# usb_board.net
KiCad netlist of a schematic drawn in Altium Designer
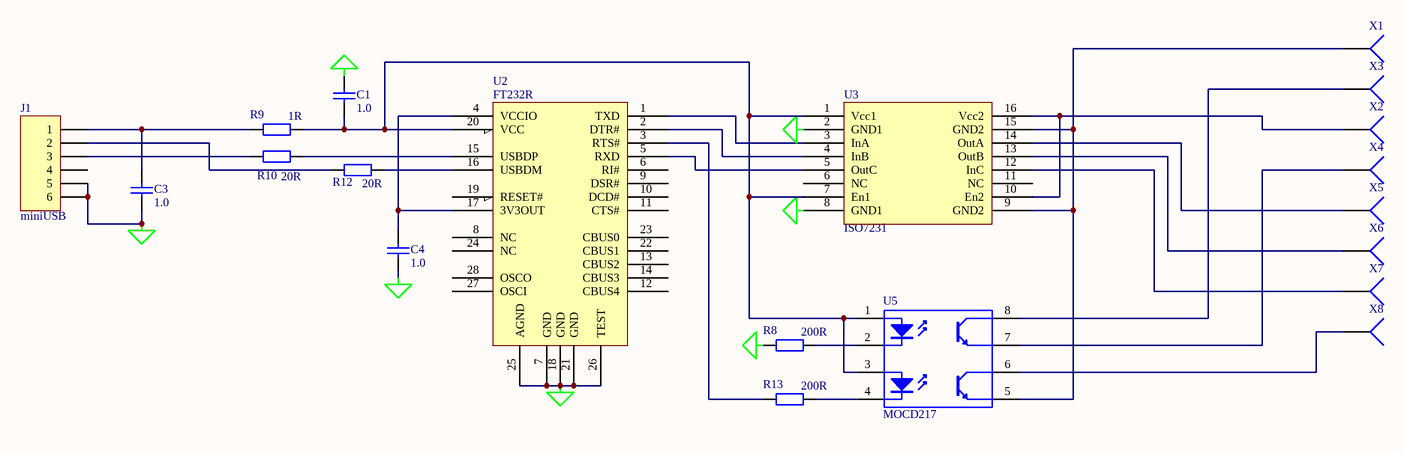
[diagram p0: usb_board.SchDoc]

(export (version "E")
  (design (tool "Eeschema 10.0.6"))
  (components
    (comp (ref "C1")
      (value "1.0")
      (footprint "_0603")
      (description "Capacitor (Semiconductor SIM Model)")
      (fields (field (name "MANUFACTURER") "Generic Components") (field (name "PUBLISHER") "Altium Limited"))
      (libsource (lib "Miscellaneous Devices") (part "Cap Semi"))
    )
    (comp (ref "C3")
      (value "1.0")
      (footprint "_0603")
      (description "Capacitor (Semiconductor SIM Model)")
      (fields (field (name "MANUFACTURER") "Generic Components") (field (name "PUBLISHER") "Altium Limited"))
      (libsource (lib "Miscellaneous Devices") (part "Cap Semi"))
    )
    (comp (ref "C4")
      (value "1.0")
      (footprint "_0603")
      (description "Capacitor (Semiconductor SIM Model)")
      (fields (field (name "MANUFACTURER") "Generic Components") (field (name "PUBLISHER") "Altium Limited"))
      (libsource (lib "Miscellaneous Devices") (part "Cap Semi"))
    )
    (comp (ref "J1")
      (value "miniUSB")
      (footprint "USBmini")
      (description "Header, 6-Pin")
      (fields (field (name "PUBLISHER") "Altium Limited"))
      (libsource (lib "Miscellaneous Connectors") (part "Header 6"))
    )
    (comp (ref "R8") (value "200R") (footprint "_0603") (libsource (lib "igorenja") (part "RES")))
    (comp (ref "R9") (value "1R") (footprint "_0603") (libsource (lib "igorenja") (part "RES")))
    (comp (ref "R10") (value "20R") (footprint "_0603") (libsource (lib "igorenja") (part "RES")))
    (comp (ref "R12") (value "20R") (footprint "_0603") (libsource (lib "igorenja") (part "RES")))
    (comp (ref "R13") (value "200R") (footprint "_0603") (libsource (lib "igorenja") (part "RES")))
    (comp (ref "U2")
      (value "FT232R")
      (footprint "SOP65P780-28L")
      (libsource (lib "igorenja") (part "FT232R"))
    )
    (comp (ref "U3") (value "ISO7231") (libsource (lib "PAL") (part "ISO7231")))
    (comp (ref "U5")
      (value "MOCD217")
      (footprint "SO-G8")
      (description "Optic")
      (libsource (lib "PAL") (part "MOCD217"))
    )
    (comp (ref "X1")
      (value "~")
      (footprint "PIN1")
      (description "Socket")
      (fields (field (name "MANUFACTURER") "Generic Components") (field (name "PUBLISHER") "Altium Limited"))
      (libsource (lib "Miscellaneous Connectors") (part "Socket"))
    )
    (comp (ref "X2")
      (value "~")
      (footprint "PIN1")
      (description "Socket")
      (fields (field (name "MANUFACTURER") "Generic Components") (field (name "PUBLISHER") "Altium Limited"))
      (libsource (lib "Miscellaneous Connectors") (part "Socket"))
    )
    (comp (ref "X3")
      (value "~")
      (footprint "PIN1")
      (description "Socket")
      (fields (field (name "MANUFACTURER") "Generic Components") (field (name "PUBLISHER") "Altium Limited"))
      (libsource (lib "Miscellaneous Connectors") (part "Socket"))
    )
    (comp (ref "X4")
      (value "~")
      (footprint "PIN1")
      (description "Socket")
      (fields (field (name "MANUFACTURER") "Generic Components") (field (name "PUBLISHER") "Altium Limited"))
      (libsource (lib "Miscellaneous Connectors") (part "Socket"))
    )
    (comp (ref "X5")
      (value "~")
      (footprint "PIN1")
      (description "Socket")
      (fields (field (name "MANUFACTURER") "Generic Components") (field (name "PUBLISHER") "Altium Limited"))
      (libsource (lib "Miscellaneous Connectors") (part "Socket"))
    )
    (comp (ref "X6")
      (value "~")
      (footprint "PIN1")
      (description "Socket")
      (fields (field (name "MANUFACTURER") "Generic Components") (field (name "PUBLISHER") "Altium Limited"))
      (libsource (lib "Miscellaneous Connectors") (part "Socket"))
    )
    (comp (ref "X7")
      (value "~")
      (footprint "PIN1")
      (description "Socket")
      (fields (field (name "MANUFACTURER") "Generic Components") (field (name "PUBLISHER") "Altium Limited"))
      (libsource (lib "Miscellaneous Connectors") (part "Socket"))
    )
    (comp (ref "X8")
      (value "~")
      (footprint "PIN1")
      (description "Socket")
      (fields (field (name "MANUFACTURER") "Generic Components") (field (name "PUBLISHER") "Altium Limited"))
      (libsource (lib "Miscellaneous Connectors") (part "Socket"))
    )
  )
  (nets
    (net (code "1") (name "GND_USB") (class "Default")
      (node (ref "C1") (pin "1") (pinfunction "1_1") (pintype "passive"))
      (node (ref "C3") (pin "1") (pinfunction "1_1") (pintype "passive"))
      (node (ref "C4") (pin "1") (pinfunction "1_1") (pintype "passive"))
      (node (ref "J1") (pin "5") (pinfunction "5_5") (pintype "passive"))
      (node (ref "J1") (pin "6") (pinfunction "6_6") (pintype "passive"))
      (node (ref "R8") (pin "1") (pinfunction "1_1") (pintype "passive"))
      (node (ref "U2") (pin "18") (pinfunction "GND_18") (pintype "passive"))
      (node (ref "U2") (pin "21") (pinfunction "GND_21") (pintype "passive"))
      (node (ref "U2") (pin "25") (pinfunction "AGND_25") (pintype "passive"))
      (node (ref "U2") (pin "26") (pinfunction "TEST_26") (pintype "passive"))
      (node (ref "U2") (pin "7") (pinfunction "GND_7") (pintype "passive"))
      (node (ref "U3") (pin "2") (pinfunction "GND1_2") (pintype "passive"))
      (node (ref "U3") (pin "8") (pinfunction "GND1_8") (pintype "passive"))
    )
    (net (code "2") (name "Net-(C3-Pad2)") (class "Default")
      (node (ref "C3") (pin "2") (pinfunction "2_2") (pintype "passive"))
      (node (ref "J1") (pin "1") (pinfunction "1_1") (pintype "passive"))
      (node (ref "R9") (pin "1") (pinfunction "1_1") (pintype "passive"))
    )
    (net (code "3") (name "Net-(J1-Pad2)") (class "Default")
      (node (ref "J1") (pin "2") (pinfunction "2_2") (pintype "passive"))
      (node (ref "R12") (pin "1") (pinfunction "1_1") (pintype "passive"))
    )
    (net (code "4") (name "Net-(J1-Pad3)") (class "Default")
      (node (ref "J1") (pin "3") (pinfunction "3_3") (pintype "passive"))
      (node (ref "R10") (pin "1") (pinfunction "1_1") (pintype "passive"))
    )
    (net (code "5") (name "Net-(R8-Pad2)") (class "Default")
      (node (ref "R8") (pin "2") (pinfunction "2_2") (pintype "passive"))
      (node (ref "U5") (pin "2") (pinfunction "K_2") (pintype "passive"))
    )
    (net (code "6") (name "Net-(R13-Pad2)") (class "Default")
      (node (ref "R13") (pin "2") (pinfunction "2_2") (pintype "passive"))
      (node (ref "U5") (pin "4") (pinfunction "K_4") (pintype "passive"))
    )
    (net (code "7") (name "Net-(U2-3V3OUT)") (class "Default")
      (node (ref "C4") (pin "2") (pinfunction "2_2") (pintype "passive"))
      (node (ref "U2") (pin "17") (pinfunction "3V3OUT_17") (pintype "passive"))
      (node (ref "U2") (pin "4") (pinfunction "VCCIO_4") (pintype "passive"))
    )
    (net (code "8") (name "Net-(U2-DTR#)") (class "Default")
      (node (ref "U2") (pin "2") (pinfunction "DTR#_2") (pintype "passive"))
      (node (ref "U3") (pin "4") (pinfunction "InB_4") (pintype "passive"))
    )
    (net (code "9") (name "Net-(U2-RTS#)") (class "Default")
      (node (ref "R13") (pin "1") (pinfunction "1_1") (pintype "passive"))
      (node (ref "U2") (pin "3") (pinfunction "RTS#_3") (pintype "passive"))
    )
    (net (code "10") (name "Net-(U2-RXD)") (class "Default")
      (node (ref "U2") (pin "5") (pinfunction "RXD_5") (pintype "passive"))
      (node (ref "U3") (pin "5") (pinfunction "OutC_5") (pintype "passive"))
    )
    (net (code "11") (name "Net-(U2-TXD)") (class "Default")
      (node (ref "U2") (pin "1") (pinfunction "TXD_1") (pintype "passive"))
      (node (ref "U3") (pin "3") (pinfunction "InA_3") (pintype "passive"))
    )
    (net (code "12") (name "Net-(U2-USBDM)") (class "Default")
      (node (ref "R12") (pin "2") (pinfunction "2_2") (pintype "passive"))
      (node (ref "U2") (pin "16") (pinfunction "USBDM_16") (pintype "passive"))
    )
    (net (code "13") (name "Net-(U2-USBDP)") (class "Default")
      (node (ref "R10") (pin "2") (pinfunction "2_2") (pintype "passive"))
      (node (ref "U2") (pin "15") (pinfunction "USBDP_15") (pintype "passive"))
    )
    (net (code "14") (name "Net-(U2-VCC)") (class "Default")
      (node (ref "C1") (pin "2") (pinfunction "2_2") (pintype "passive"))
      (node (ref "R9") (pin "2") (pinfunction "2_2") (pintype "passive"))
      (node (ref "U2") (pin "20") (pinfunction "VCC_20") (pintype "passive"))
      (node (ref "U3") (pin "1") (pinfunction "Vcc1_1") (pintype "passive"))
      (node (ref "U3") (pin "7") (pinfunction "En1_7") (pintype "passive"))
      (node (ref "U5") (pin "1") (pinfunction "A_1") (pintype "passive"))
      (node (ref "U5") (pin "3") (pinfunction "A_3") (pintype "passive"))
    )
    (net (code "15") (name "Net-(U3-En2)") (class "Default")
      (node (ref "U3") (pin "10") (pinfunction "En2_10") (pintype "passive"))
      (node (ref "U3") (pin "16") (pinfunction "Vcc2_16") (pintype "passive"))
      (node (ref "X2") (pin "1") (pinfunction "1_1") (pintype "passive"))
    )
    (net (code "16") (name "Net-(U3-GND2-Pad15)") (class "Default")
      (node (ref "U3") (pin "15") (pinfunction "GND2_15") (pintype "passive"))
      (node (ref "U3") (pin "9") (pinfunction "GND2_9") (pintype "passive"))
      (node (ref "U5") (pin "5") (pinfunction "E_5") (pintype "passive"))
      (node (ref "X1") (pin "1") (pinfunction "1_1") (pintype "passive"))
    )
    (net (code "17") (name "Net-(U3-InC)") (class "Default")
      (node (ref "U3") (pin "12") (pinfunction "InC_12") (pintype "passive"))
      (node (ref "X7") (pin "1") (pinfunction "1_1") (pintype "passive"))
    )
    (net (code "18") (name "Net-(U3-OutA)") (class "Default")
      (node (ref "U3") (pin "14") (pinfunction "OutA_14") (pintype "passive"))
      (node (ref "X5") (pin "1") (pinfunction "1_1") (pintype "passive"))
    )
    (net (code "19") (name "Net-(U3-OutB)") (class "Default")
      (node (ref "U3") (pin "13") (pinfunction "OutB_13") (pintype "passive"))
      (node (ref "X6") (pin "1") (pinfunction "1_1") (pintype "passive"))
    )
    (net (code "20") (name "Net-(U5-C-Pad6)") (class "Default")
      (node (ref "U5") (pin "6") (pinfunction "C_6") (pintype "passive"))
      (node (ref "X8") (pin "1") (pinfunction "1_1") (pintype "passive"))
    )
    (net (code "21") (name "Net-(U5-C-Pad8)") (class "Default")
      (node (ref "U5") (pin "8") (pinfunction "C_8") (pintype "passive"))
      (node (ref "X3") (pin "1") (pinfunction "1_1") (pintype "passive"))
    )
    (net (code "22") (name "Net-(U5-E-Pad7)") (class "Default")
      (node (ref "U5") (pin "7") (pinfunction "E_7") (pintype "passive"))
      (node (ref "X4") (pin "1") (pinfunction "1_1") (pintype "passive"))
    )
    (net (code "23") (name "unconnected-(J1-Pad4)") (class "Default")
      (node (ref "J1") (pin "4") (pinfunction "4_4") (pintype "passive"))
    )
    (net (code "24") (name "unconnected-(U2-CBUS0-Pad23)") (class "Default")
      (node (ref "U2") (pin "23") (pinfunction "CBUS0_23") (pintype "passive"))
    )
    (net (code "25") (name "unconnected-(U2-CBUS1-Pad22)") (class "Default")
      (node (ref "U2") (pin "22") (pinfunction "CBUS1_22") (pintype "passive"))
    )
    (net (code "26") (name "unconnected-(U2-CBUS2-Pad13)") (class "Default")
      (node (ref "U2") (pin "13") (pinfunction "CBUS2_13") (pintype "passive"))
    )
    (net (code "27") (name "unconnected-(U2-CBUS3-Pad14)") (class "Default")
      (node (ref "U2") (pin "14") (pinfunction "CBUS3_14") (pintype "passive"))
    )
    (net (code "28") (name "unconnected-(U2-CBUS4-Pad12)") (class "Default")
      (node (ref "U2") (pin "12") (pinfunction "CBUS4_12") (pintype "passive"))
    )
    (net (code "29") (name "unconnected-(U2-CTS#-Pad11)") (class "Default")
      (node (ref "U2") (pin "11") (pinfunction "CTS#_11") (pintype "passive"))
    )
    (net (code "30") (name "unconnected-(U2-DCD#-Pad10)") (class "Default")
      (node (ref "U2") (pin "10") (pinfunction "DCD#_10") (pintype "passive"))
    )
    (net (code "31") (name "unconnected-(U2-DSR#-Pad9)") (class "Default")
      (node (ref "U2") (pin "9") (pinfunction "DSR#_9") (pintype "passive"))
    )
    (net (code "32") (name "unconnected-(U2-NC-Pad8)") (class "Default")
      (node (ref "U2") (pin "8") (pinfunction "NC_8") (pintype "passive"))
    )
    (net (code "33") (name "unconnected-(U2-NC-Pad24)") (class "Default")
      (node (ref "U2") (pin "24") (pinfunction "NC_24") (pintype "passive"))
    )
    (net (code "34") (name "unconnected-(U2-OSCI-Pad27)") (class "Default")
      (node (ref "U2") (pin "27") (pinfunction "OSCI_27") (pintype "passive"))
    )
    (net (code "35") (name "unconnected-(U2-OSCO-Pad28)") (class "Default")
      (node (ref "U2") (pin "28") (pinfunction "OSCO_28") (pintype "passive"))
    )
    (net (code "36") (name "unconnected-(U2-RESET#-Pad19)") (class "Default")
      (node (ref "U2") (pin "19") (pinfunction "RESET#_19") (pintype "passive"))
    )
    (net (code "37") (name "unconnected-(U2-RI#-Pad6)") (class "Default")
      (node (ref "U2") (pin "6") (pinfunction "RI#_6") (pintype "passive"))
    )
    (net (code "38") (name "unconnected-(U3-NC-Pad6)") (class "Default")
      (node (ref "U3") (pin "6") (pinfunction "NC_6") (pintype "passive"))
    )
    (net (code "39") (name "unconnected-(U3-NC-Pad11)") (class "Default")
      (node (ref "U3") (pin "11") (pinfunction "NC_11") (pintype "passive"))
    )
  )
)
